# BatUSBSwitchRev2.net
KiCad netlist of a schematic drawn in Altium Designer
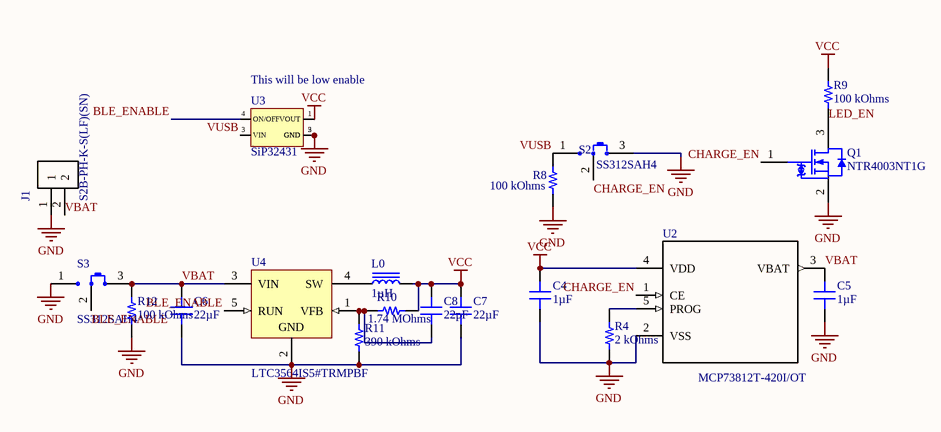
[diagram p0: BatUSBSwitchRev2.SchDoc]

(export (version "E")
  (design (tool "Eeschema 10.0.6"))
  (components
    (comp (ref "C4")
      (value "1µF")
      (footprint "CAP 0805_2012")
      (description "CAP CER 1UF 35V X7R 0805")
      (fields
        (field (name "PART NUMBER") "GRM219R7YA105KA12D")
        (field (name "MANUFACTURER") "Murata Electronics")
      )
      (libsource (lib "Celestial Altium Library - altium_library") (part "Capacitor"))
    )
    (comp (ref "C5")
      (value "1µF")
      (footprint "CAP 0805_2012")
      (description "CAP CER 1UF 35V X7R 0805")
      (fields
        (field (name "PART NUMBER") "GRM219R7YA105KA12D")
        (field (name "MANUFACTURER") "Murata Electronics")
      )
      (libsource (lib "Celestial Altium Library - altium_library") (part "Capacitor"))
    )
    (comp (ref "C6")
      (value "22µF")
      (footprint "CAP 0805_2012")
      (description "CAP CER 22UF 6.3V X5R 0805")
      (fields
        (field (name "PART NUMBER") "GRM21BR60J226ME39K")
        (field (name "MANUFACTURER") "Murata Electronics")
      )
      (libsource (lib "Celestial Altium Library - altium_library") (part "Capacitor"))
    )
    (comp (ref "C7")
      (value "22µF")
      (footprint "CAP 0805_2012")
      (description "CAP CER 22UF 6.3V X5R 0805")
      (fields
        (field (name "PART NUMBER") "GRM21BR60J226ME39K")
        (field (name "MANUFACTURER") "Murata Electronics")
      )
      (libsource (lib "Celestial Altium Library - altium_library") (part "Capacitor"))
    )
    (comp (ref "C8")
      (value "22pF")
      (footprint "CAP 0805_2012")
      (description "CAP CER 22PF 250V C0G/NP0 0805")
      (fields
        (field (name "PART NUMBER") "GRM21A5C2E220JW01D")
        (field (name "MANUFACTURER") "Murata Electronics")
      )
      (libsource (lib "Celestial Altium Library - altium_library") (part "Capacitor"))
    )
    (comp (ref "J1")
      (value "S2B-PH-K-S(LF)(SN)")
      (footprint "JST_S2B-PH-K-S(LF)(SN)")
      (description "PH Series 2 Position 2.0 mm Through Hole Side Entry Shrouded Header")
      (fields (field (name "MP") "S2B-PH-K-S_LF__SN_") (field (name "DIGI-KEY_PART_NUMBER") "455-1719-ND"))
      (libsource (lib "S2B-PH-K-S_LF__SN_") (part "S2B-PH-K-S(LF)(SN)"))
    )
    (comp (ref "L0")
      (value "1µH")
      (footprint "IND 0806_2016")
      (description "FIXED IND 1UH 2.9A 48 MOHM SMD")
      (fields
        (field (name "PART NUMBER") "DFE201612E-1R0M=P2")
        (field (name "MANUFACTURER") "Murata Electronics")
      )
      (libsource (lib "Celestial Altium Library - altium_library") (part "Inductor"))
    )
    (comp (ref "Q1")
      (value "NTR4003NT1G")
      (footprint "ONSC-SOT-23-3-318-08_V")
      (description "Small Signal MOSFET, 30 V, 0.56 A, Single N-Channe, 3-Pin SOT-23, Pb-Free, Tape and Reel")
      (fields (field (name "MANUFACTURER") "On Semiconductor"))
      (libsource (lib "On_Semiconductor_NTR4003NT1G") (part "NTR4003NT1G"))
    )
    (comp (ref "R4")
      (value "2 kOhms")
      (footprint "RES 0805_2012")
      (description "RES 2K OHM 0.1% 1/8W 0805")
      (fields
        (field (name "PART NUMBER") "ERA-6AEB202V")
        (field (name "MANUFACTURER") "Panasonic Electronic Components")
      )
      (libsource (lib "Celestial Altium Library - altium_library") (part "Resistor"))
    )
    (comp (ref "R8")
      (value "100 kOhms")
      (footprint "RES 0805_2012")
      (description "RES SMD 100K OHM 1% 1/8W 0805")
      (fields
        (field (name "PART NUMBER") "ERJ-6ENF1003V")
        (field (name "MANUFACTURER") "Panasonic Electronic Components")
      )
      (libsource (lib "Celestial Altium Library - altium_library") (part "Resistor"))
    )
    (comp (ref "R9")
      (value "100 kOhms")
      (footprint "RES 0805_2012")
      (description "RES SMD 100K OHM 1% 1/8W 0805")
      (fields
        (field (name "PART NUMBER") "ERJ-6ENF1003V")
        (field (name "MANUFACTURER") "Panasonic Electronic Components")
      )
      (libsource (lib "Celestial Altium Library - altium_library") (part "Resistor"))
    )
    (comp (ref "R10")
      (value "1.74 MOhms")
      (footprint "RES 0805_2012")
      (description "RES SMD 1.74M OHM 1% 1/8W 0805")
      (fields
        (field (name "PART NUMBER") "ERJ-6ENF1744V")
        (field (name "MANUFACTURER") "Panasonic Electronic Components")
      )
      (libsource (lib "Celestial Altium Library - altium_library") (part "Resistor"))
    )
    (comp (ref "R11")
      (value "390 kOhms")
      (footprint "RES 0805_2012")
      (description "RES 390K OHM 0.1% 1/8W 0805")
      (fields
        (field (name "PART NUMBER") "ERA-6AEB394V")
        (field (name "MANUFACTURER") "Panasonic Electronic Components")
      )
      (libsource (lib "Celestial Altium Library - altium_library") (part "Resistor"))
    )
    (comp (ref "R12")
      (value "100 kOhms")
      (footprint "RES 0805_2012")
      (description "RES SMD 100K OHM 1% 1/8W 0805")
      (fields
        (field (name "PART NUMBER") "ERJ-6ENF1003V")
        (field (name "MANUFACTURER") "Panasonic Electronic Components")
      )
      (libsource (lib "Celestial Altium Library - altium_library") (part "Resistor"))
    )
    (comp (ref "S2")
      (value "SS312SAH4")
      (footprint "NKK SS312SAH4")
      (description "SWITCH SLIDE SPDT 0.4VA 28V")
      (fields (field (name "MANUFACTURER") "NKK Switches"))
      (libsource (lib "Celestial Altium Library - altium_library") (part "NKK SS312"))
    )
    (comp (ref "S3")
      (value "SS312SAH4")
      (footprint "NKK SS312SAH4")
      (description "SWITCH SLIDE SPDT 0.4VA 28V")
      (fields (field (name "MANUFACTURER") "NKK Switches"))
      (libsource (lib "Celestial Altium Library - altium_library") (part "NKK SS312"))
    )
    (comp (ref "U2")
      (value "MCP73812T-420I/OT")
      (footprint "*SOT95P270X145-5N")
      (description "Sot23 Simple Low-Cost Integrated Li-Ion/Li-Poly Charge Mgnt Controller, 4.2v Vre")
      (fields (field (name "MF") "Microchip"))
      (libsource (lib "MCP73812T-420I_OT") (part "MCP73812T-420I/OT"))
    )
    (comp (ref "U3")
      (value "SiP32431")
      (footprint "SiP32431_TDFN4")
      (description "Ultra low quiescent current load switch, low enable")
      (libsource (lib "SiP32431") (part "SiP32431"))
    )
    (comp (ref "U4")
      (value "LTC3564IS5#TRMPBF")
      (footprint "LT-S5-5-TSOT-23_N")
      (fields (field (name "MANUFACTURER") "Linear Technology"))
      (libsource (lib "Linear_Technology_LTC3564IS5_TRMPBF") (part "LTC3564IS5#TRMPBF"))
    )
  )
  (nets
    (net (code "1") (name "/BLE_ENABLE") (class "Default")
      (node (ref "S3") (pin "2") (pinfunction "COM_2") (pintype "passive"))
      (node (ref "U3") (pin "4") (pinfunction "ON/OFF_4") (pintype "passive"))
      (node (ref "U4") (pin "5") (pinfunction "RUN_5") (pintype "input"))
    )
    (net (code "2") (name "/CHARGE_EN") (class "Default")
      (node (ref "Q1") (pin "1") (pinfunction "G_1") (pintype "passive"))
      (node (ref "S2") (pin "2") (pinfunction "COM_2") (pintype "passive"))
      (node (ref "U2") (pin "1") (pinfunction "CE_1") (pintype "input"))
    )
    (net (code "3") (name "/LED_EN") (class "Default")
      (node (ref "Q1") (pin "3") (pinfunction "D_3") (pintype "passive"))
      (node (ref "R9") (pin "1") (pinfunction "1_1") (pintype "passive"))
    )
    (net (code "4") (name "/VBAT") (class "Default")
      (node (ref "C5") (pin "2") (pinfunction "2_2") (pintype "passive"))
      (node (ref "C6") (pin "2") (pinfunction "2_2") (pintype "passive"))
      (node (ref "J1") (pin "2") (pinfunction "2_2") (pintype "passive"))
      (node (ref "R12") (pin "2") (pinfunction "2_2") (pintype "passive"))
      (node (ref "S3") (pin "3") (pinfunction "3_3") (pintype "passive"))
      (node (ref "U2") (pin "3") (pinfunction "VBAT_3") (pintype "output"))
      (node (ref "U4") (pin "3") (pinfunction "VIN_3") (pintype "power_in"))
    )
    (net (code "5") (name "/VUSB") (class "Default")
      (node (ref "R8") (pin "2") (pinfunction "2_2") (pintype "passive"))
      (node (ref "S2") (pin "1") (pinfunction "1_1") (pintype "passive"))
      (node (ref "U3") (pin "3") (pinfunction "VIN_3") (pintype "input"))
    )
    (net (code "6") (name "GND") (class "Default")
      (node (ref "C4") (pin "1") (pinfunction "1_1") (pintype "passive"))
      (node (ref "C5") (pin "1") (pinfunction "1_1") (pintype "passive"))
      (node (ref "C6") (pin "1") (pinfunction "1_1") (pintype "passive"))
      (node (ref "C7") (pin "1") (pinfunction "1_1") (pintype "passive"))
      (node (ref "J1") (pin "1") (pinfunction "1_1") (pintype "passive"))
      (node (ref "Q1") (pin "2") (pinfunction "S_2") (pintype "passive"))
      (node (ref "R11") (pin "1") (pinfunction "1_1") (pintype "passive"))
      (node (ref "R12") (pin "1") (pinfunction "1_1") (pintype "passive"))
      (node (ref "R4") (pin "1") (pinfunction "1_1") (pintype "passive"))
      (node (ref "R8") (pin "1") (pinfunction "1_1") (pintype "passive"))
      (node (ref "S2") (pin "3") (pinfunction "3_3") (pintype "passive"))
      (node (ref "S3") (pin "1") (pinfunction "1_1") (pintype "passive"))
      (node (ref "U2") (pin "2") (pinfunction "VSS_2") (pintype "power_in"))
      (node (ref "U3") (pin "2") (pinfunction "GND_2") (pintype "power_in"))
      (node (ref "U3") (pin "5") (pinfunction "GND_5") (pintype "power_in"))
      (node (ref "U4") (pin "2") (pinfunction "GND_2") (pintype "power_in"))
    )
    (net (code "7") (name "Net-(U2-PROG)") (class "Default")
      (node (ref "R4") (pin "2") (pinfunction "2_2") (pintype "passive"))
      (node (ref "U2") (pin "5") (pinfunction "PROG_5") (pintype "input"))
    )
    (net (code "8") (name "Net-(U4-SW)") (class "Default")
      (node (ref "L0") (pin "1") (pinfunction "1_1") (pintype "passive"))
      (node (ref "U4") (pin "4") (pinfunction "SW_4") (pintype "power_in"))
    )
    (net (code "9") (name "Net-(U4-VFB)") (class "Default")
      (node (ref "C8") (pin "1") (pinfunction "1_1") (pintype "passive"))
      (node (ref "R10") (pin "1") (pinfunction "1_1") (pintype "passive"))
      (node (ref "R11") (pin "2") (pinfunction "2_2") (pintype "passive"))
      (node (ref "U4") (pin "1") (pinfunction "VFB_1") (pintype "input"))
    )
    (net (code "10") (name "VCC") (class "Default")
      (node (ref "C4") (pin "2") (pinfunction "2_2") (pintype "passive"))
      (node (ref "C7") (pin "2") (pinfunction "2_2") (pintype "passive"))
      (node (ref "C8") (pin "2") (pinfunction "2_2") (pintype "passive"))
      (node (ref "L0") (pin "2") (pinfunction "2_2") (pintype "passive"))
      (node (ref "R10") (pin "2") (pinfunction "2_2") (pintype "passive"))
      (node (ref "R9") (pin "2") (pinfunction "2_2") (pintype "passive"))
      (node (ref "U2") (pin "4") (pinfunction "VDD_4") (pintype "power_in"))
      (node (ref "U3") (pin "1") (pinfunction "VOUT_1") (pintype "output"))
    )
  )
)
